# Shield_sch.net
KiCad netlist of a schematic drawn in Altium Designer
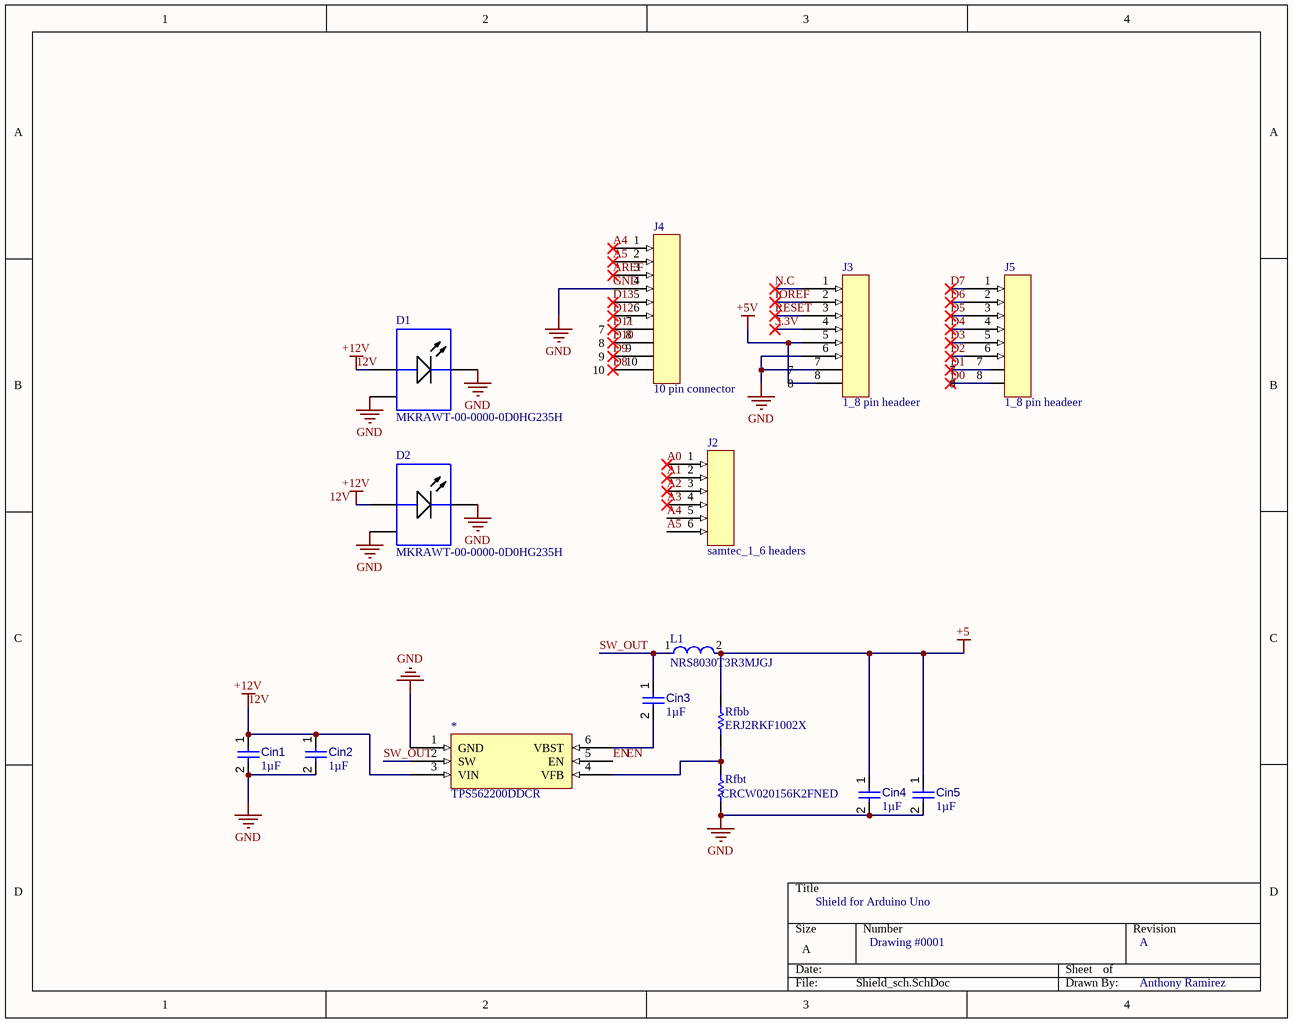
[diagram p0: Shield_sch.SchDoc]

(export (version "E")
  (design (tool "Eeschema 10.0.6"))
  (components
    (comp (ref "*")
      (value "TPS562200DDCR")
      (footprint "SOT95P245X110-6N")
      (description "Switching Regulator, 2A, 650kHz Switching Freq-Max, PDSO6")
      (libsource (lib "Anthony's_Test_Boards") (part "TPS562200DDCR-Symbol-1"))
    )
    (comp (ref "Cin1")
      (value "1µF")
      (footprint "CAPC1608X90X40LL10T20")
      (description "Chip Capacitor, 1 uF, +/- 10%, 25 V, 0603 (1608 Metric)")
      (fields (field (name "TOLERANCE") "10%") (field (name "Comment") "Capacitor 1 uF +/- 10% 25 V 0603"))
      (libsource (lib "Anthony's_Test_Boards") (part "CAP-NP-2"))
    )
    (comp (ref "Cin2")
      (value "1µF")
      (footprint "CAPC1608X90X40LL10T20")
      (description "Chip Capacitor, 1 uF, +/- 10%, 25 V, 0603 (1608 Metric)")
      (fields (field (name "TOLERANCE") "10%") (field (name "Comment") "Capacitor 1 uF +/- 10% 25 V 0603"))
      (libsource (lib "Anthony's_Test_Boards") (part "CAP-NP-2"))
    )
    (comp (ref "Cin3")
      (value "1µF")
      (footprint "CAPC1608X90X40LL10T20")
      (description "Chip Capacitor, 1 uF, +/- 10%, 25 V, 0603 (1608 Metric)")
      (fields (field (name "TOLERANCE") "10%") (field (name "Comment") "Capacitor 1 uF +/- 10% 25 V 0603"))
      (libsource (lib "Anthony's_Test_Boards") (part "CAP-NP-2"))
    )
    (comp (ref "Cin4")
      (value "1µF")
      (footprint "CAPC1608X90X40LL10T20")
      (description "Chip Capacitor, 1 uF, +/- 10%, 25 V, 0603 (1608 Metric)")
      (fields (field (name "TOLERANCE") "10%") (field (name "Comment") "Capacitor 1 uF +/- 10% 25 V 0603"))
      (libsource (lib "Anthony's_Test_Boards") (part "CAP-NP-2"))
    )
    (comp (ref "Cin5")
      (value "1µF")
      (footprint "CAPC1608X90X40LL10T20")
      (description "Chip Capacitor, 1 uF, +/- 10%, 25 V, 0603 (1608 Metric)")
      (fields (field (name "TOLERANCE") "10%") (field (name "Comment") "Capacitor 1 uF +/- 10% 25 V 0603"))
      (libsource (lib "Anthony's_Test_Boards") (part "CAP-NP-2"))
    )
    (comp (ref "D1")
      (value "MKRAWT-00-0000-0D0HG235H")
      (footprint "CREE-MK-R-2_V")
      (description "LED, White, 12 V, 2-Pin SMD, RoHS, Tape and Reel")
      (libsource (lib "Altium Content Vault") (part "LED_WHITE-3"))
    )
    (comp (ref "D2")
      (value "MKRAWT-00-0000-0D0HG235H")
      (footprint "CREE-MK-R-2_V")
      (description "LED, White, 12 V, 2-Pin SMD, RoHS, Tape and Reel")
      (libsource (lib "Altium Content Vault") (part "LED_WHITE-3"))
    )
    (comp (ref "J2")
      (value "samtec_1_6 headers")
      (footprint "samtec_1_6 headers-Footprint-1")
      (description "1 row 6 pin headers with 1.27mm radius for arduino shield")
      (libsource (lib "Anthony's_Test_Boards") (part "samtec_1_6 headers-Symbol-1"))
    )
    (comp (ref "J3")
      (value "1_8 pin headeer")
      (footprint "1_8_Pin headers-Footprint-1")
      (libsource (lib "Anthony's_Test_Boards") (part "New symbol 1"))
    )
    (comp (ref "J4")
      (value "10 pin connector")
      (footprint "10 pin connector-Footprint-1")
      (description "10pin connector")
      (libsource (lib "Anthony's_Test_Boards") (part "10 pin connector-Symbol-1"))
    )
    (comp (ref "J5")
      (value "1_8 pin headeer")
      (footprint "1_8_Pin headers-Footprint-1")
      (libsource (lib "Anthony's_Test_Boards") (part "New symbol 1"))
    )
    (comp (ref "L1")
      (value "NRS8030T3R3MJGJ")
      (footprint "FP-NRS8030-MFG")
      (description "Inductor Power Shielded Wirewound 3.3uH 20% 100KHz Ferrite 4.2A 24.7mΩ DCR T/R")
      (fields (field (name "TOLERANCE") "20%"))
      (libsource (lib "Altium Content Vault") (part "725321dda6339637d4d059423bc1c3c"))
    )
    (comp (ref "Rfbb")
      (value "ERJ2RKF1002X")
      (footprint "RESC1005X40X25LL05T05")
      (description "Chip Resistor, 10 KOhm, +/- 1%, 0.1 W, -55 to 155 degC, 0402 (1005 Metric), RoHS, Tape and Reel")
      (fields (field (name "TOLERANCE") "1%") (field (name "MANUFACTURER") "Panasonic"))
      (libsource (lib "Altium Content Vault") (part "RES-2"))
    )
    (comp (ref "Rfbt")
      (value "CRCW020156K2FNED")
      (footprint "RESC0603X28X15NL05T05")
      (fields (field (name "MANUFACTURER") "Vishay Dale"))
      (libsource (lib "Altium Content Vault") (part "RES"))
    )
  )
  (nets
    (net (code "1") (name "+5") (class "Default")
      (node (ref "Cin4") (pin "1") (pinfunction "1_1") (pintype "passive"))
      (node (ref "Cin5") (pin "1") (pinfunction "1_1") (pintype "passive"))
      (node (ref "L1") (pin "2") (pinfunction "2_2") (pintype "passive"))
      (node (ref "Rfbb") (pin "1") (pinfunction "1_1") (pintype "passive"))
    )
    (net (code "2") (name "+5V") (class "Default") (node (ref "J3") (pin "5") (pintype "input")))
    (net (code "3") (name "+12V") (class "Default")
      (node (ref "*") (pin "3") (pinfunction "VIN_3") (pintype "input"))
      (node (ref "Cin1") (pin "1") (pinfunction "1_1") (pintype "passive"))
      (node (ref "Cin2") (pin "1") (pinfunction "1_1") (pintype "passive"))
      (node (ref "D1") (pin "1") (pinfunction "A_1") (pintype "passive"))
      (node (ref "D2") (pin "1") (pinfunction "A_1") (pintype "passive"))
    )
    (net (code "4") (name "/3.3V") (class "Default") (node (ref "J3") (pin "4") (pintype "input+no_connect")))
    (net (code "5") (name "/A0") (class "Default") (node (ref "J2") (pin "1") (pintype "input+no_connect")))
    (net (code "6") (name "/A1") (class "Default") (node (ref "J2") (pin "2") (pintype "input+no_connect")))
    (net (code "7") (name "/A2") (class "Default") (node (ref "J2") (pin "3") (pintype "input+no_connect")))
    (net (code "8") (name "/A3") (class "Default") (node (ref "J2") (pin "4") (pintype "input+no_connect")))
    (net (code "9") (name "/A4") (class "Default")
      (node (ref "J2") (pin "5") (pintype "input"))
      (node (ref "J4") (pin "1") (pintype "input"))
    )
    (net (code "10") (name "/A5") (class "Default")
      (node (ref "J2") (pin "6") (pintype "input"))
      (node (ref "J4") (pin "2") (pintype "input"))
    )
    (net (code "11") (name "/AREF") (class "Default")
      (node (ref "J4") (pin "3") (pintype "input+no_connect"))
    )
    (net (code "14") (name "/D2") (class "Default") (node (ref "J5") (pin "6") (pintype "input+no_connect")))
    (net (code "15") (name "/D3") (class "Default") (node (ref "J5") (pin "5") (pintype "input+no_connect")))
    (net (code "16") (name "/D4") (class "Default") (node (ref "J5") (pin "4") (pintype "input+no_connect")))
    (net (code "17") (name "/D5") (class "Default") (node (ref "J5") (pin "3") (pintype "input+no_connect")))
    (net (code "18") (name "/D6") (class "Default") (node (ref "J5") (pin "2") (pintype "input+no_connect")))
    (net (code "19") (name "/D7") (class "Default") (node (ref "J5") (pin "1") (pintype "input+no_connect")))
    (net (code "24") (name "/D12") (class "Default") (node (ref "J4") (pin "6") (pintype "input+no_connect")))
    (net (code "25") (name "/D13") (class "Default") (node (ref "J4") (pin "5") (pintype "input+no_connect")))
    (net (code "26") (name "/EN") (class "Default")
      (node (ref "*") (pin "5") (pinfunction "EN_5") (pintype "input"))
    )
    (net (code "27") (name "/IOREF") (class "Default")
      (node (ref "J3") (pin "2") (pintype "input+no_connect"))
    )
    (net (code "28") (name "/N.C") (class "Default") (node (ref "J3") (pin "1") (pintype "input+no_connect")))
    (net (code "29") (name "/RESET") (class "Default")
      (node (ref "J3") (pin "3") (pintype "input+no_connect"))
    )
    (net (code "30") (name "/SW_OUT") (class "Default")
      (node (ref "*") (pin "2") (pinfunction "SW_2") (pintype "input"))
      (node (ref "Cin3") (pin "1") (pinfunction "1_1") (pintype "passive"))
      (node (ref "L1") (pin "1") (pinfunction "1_1") (pintype "passive"))
    )
    (net (code "31") (name "GND") (class "Default")
      (node (ref "*") (pin "1") (pinfunction "GND_1") (pintype "input"))
      (node (ref "Cin1") (pin "2") (pinfunction "2_2") (pintype "passive"))
      (node (ref "Cin2") (pin "2") (pinfunction "2_2") (pintype "passive"))
      (node (ref "Cin4") (pin "2") (pinfunction "2_2") (pintype "passive"))
      (node (ref "Cin5") (pin "2") (pinfunction "2_2") (pintype "passive"))
      (node (ref "D1") (pin "2") (pinfunction "K_2") (pintype "passive"))
      (node (ref "D1") (pin "3") (pinfunction "EP_3") (pintype "passive"))
      (node (ref "D2") (pin "2") (pinfunction "K_2") (pintype "passive"))
      (node (ref "D2") (pin "3") (pinfunction "EP_3") (pintype "passive"))
      (node (ref "J3") (pin "6") (pintype "input"))
      (node (ref "J4") (pin "4") (pintype "input"))
      (node (ref "Rfbt") (pin "2") (pinfunction "2_2") (pintype "passive"))
    )
    (net (code "32") (name "Net-(*-VBST)") (class "Default")
      (node (ref "*") (pin "6") (pinfunction "VBST_6") (pintype "input"))
      (node (ref "Cin3") (pin "2") (pinfunction "2_2") (pintype "passive"))
    )
    (net (code "33") (name "Net-(*-VFB)") (class "Default")
      (node (ref "*") (pin "4") (pinfunction "VFB_4") (pintype "input"))
      (node (ref "Rfbb") (pin "2") (pinfunction "2_2") (pintype "passive"))
      (node (ref "Rfbt") (pin "1") (pinfunction "1_1") (pintype "passive"))
    )
    (net (code "34") (name "unconnected-(J3-Pad7)") (class "Default")
      (node (ref "J3") (pin "7") (pinfunction "7_7") (pintype "passive"))
    )
    (net (code "35") (name "unconnected-(J3-Pad8)") (class "Default")
      (node (ref "J3") (pin "8") (pinfunction "8_8") (pintype "passive"))
    )
    (net (code "36") (name "unconnected-(J4-Pad7)") (class "Default")
      (node (ref "J4") (pin "7") (pinfunction "7_7") (pintype "passive"))
    )
    (net (code "37") (name "unconnected-(J4-Pad8)") (class "Default")
      (node (ref "J4") (pin "8") (pinfunction "8_8") (pintype "passive"))
    )
    (net (code "38") (name "unconnected-(J4-Pad9)") (class "Default")
      (node (ref "J4") (pin "9") (pinfunction "9_9") (pintype "passive"))
    )
    (net (code "39") (name "unconnected-(J4-Pad10)") (class "Default")
      (node (ref "J4") (pin "10") (pinfunction "10_10") (pintype "passive"))
    )
    (net (code "40") (name "unconnected-(J5-Pad7)") (class "Default")
      (node (ref "J5") (pin "7") (pinfunction "7_7") (pintype "passive"))
    )
    (net (code "41") (name "unconnected-(J5-Pad8)") (class "Default")
      (node (ref "J5") (pin "8") (pinfunction "8_8") (pintype "passive"))
    )
  )
)
